# TEST_PROD_BATT_PANEL.net
KiCad netlist of a schematic drawn in EAGLE
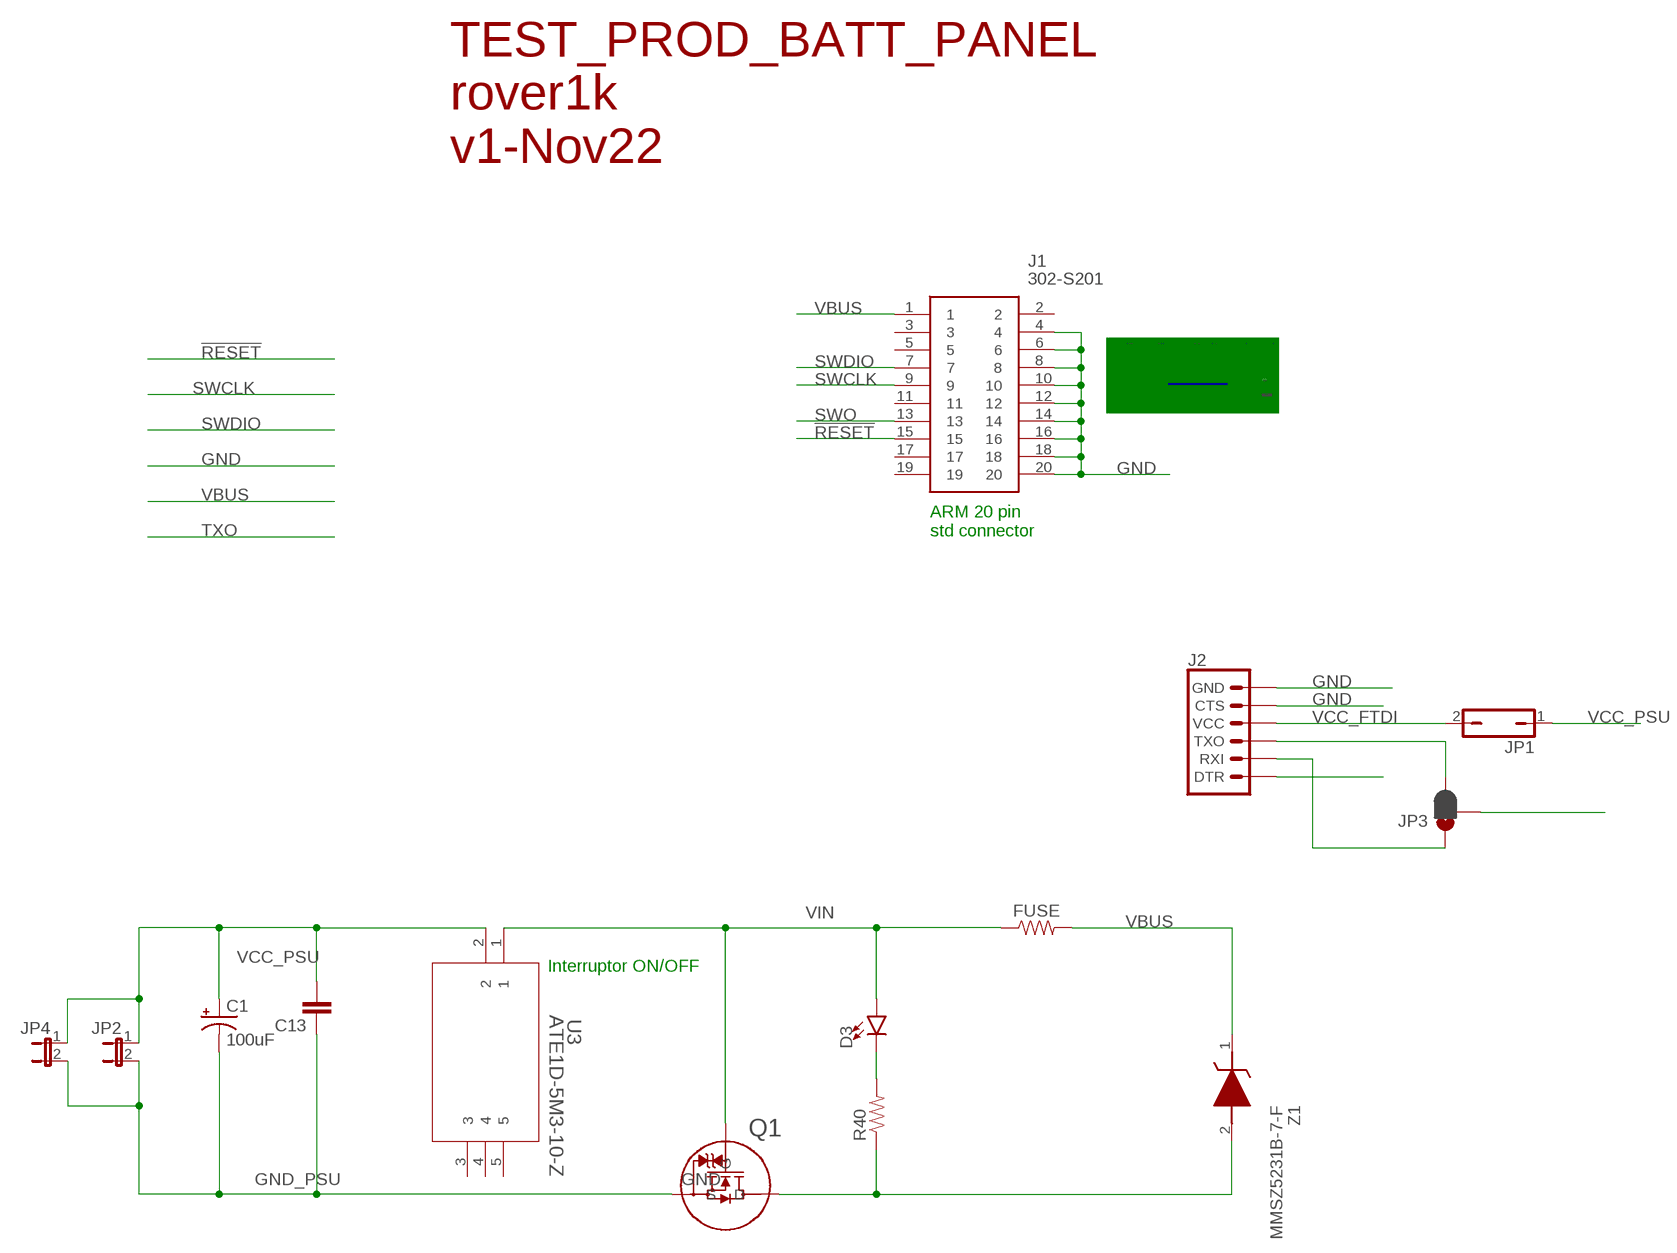
[diagram p0: schematic, sheet 1]

(export (version "E")
  (design (tool "Eeschema 10.0.6"))
  (components
    (comp (ref "C1")
      (value "100uF")
      (footprint "eagle-import:CPOL-RADIAL-2.5MM-6.5MM")
      (libsource (lib "eagle-import") (part "100UF-POLAR-RADIAL-2.5MM-25V-20%"))
    )
    (comp (ref "C13")
      (value "C-EUC0805")
      (footprint "eagle-import:C0805")
      (libsource (lib "eagle-import") (part "C-EUC0805"))
    )
    (comp (ref "D3")
      (value "LED3MM")
      (footprint "eagle-import:LED_3MM")
      (libsource (lib "eagle-import") (part "LED3MM"))
    )
    (comp (ref "FUSE")
      (value "RESISTOR0805")
      (footprint "eagle-import:0805")
      (libsource (lib "eagle-import") (part "RESISTOR0805"))
    )
    (comp (ref "J1")
      (value "302-S201")
      (footprint "eagle-import:SHDR20W66P254_2X10_3300X905X90")
      (libsource (lib "eagle-import") (part "302-S201"))
    )
    (comp (ref "J2")
      (value "6_PIN_SERIAL_TARGET")
      (footprint "eagle-import:1X06")
      (libsource (lib "eagle-import") (part "6_PIN_SERIAL_TARGET"))
    )
    (comp (ref "JP1")
      (value "JP1Q")
      (footprint "eagle-import:JP1")
      (libsource (lib "eagle-import") (part "JP1Q"))
    )
    (comp (ref "JP2")
      (value "JP1E")
      (footprint "eagle-import:JP1")
      (libsource (lib "eagle-import") (part "JP1E"))
    )
    (comp (ref "JP3")
      (value "JUMPER-SMT_3_1-NC_PASTE_NO-SILK")
      (footprint "eagle-import:SMT-JUMPER_3_1-NC_PASTE_NO-SILK")
      (libsource (lib "eagle-import") (part "JUMPER-SMT_3_1-NC_PASTE_NO-SILK"))
    )
    (comp (ref "JP4")
      (value "JP1E")
      (footprint "eagle-import:JP1")
      (libsource (lib "eagle-import") (part "JP1E"))
    )
    (comp (ref "Q1")
      (value "PJA3416AE_R1_00001")
      (footprint "eagle-import:SOT23_PJA3416_PNJ")
      (fields (field (name "COPYRIGHT") "Copyright (C) 2022 Ultra Librarian. All rights reserved."))
      (libsource (lib "eagle-import") (part "PJA3416AE_R1_00001"))
    )
    (comp (ref "R40")
      (value "10K")
      (footprint "eagle-import:0805")
      (libsource (lib "eagle-import") (part "RESISTOR0805-RES"))
    )
    (comp (ref "U3")
      (value "ATE1D-5M3-10-Z")
      (footprint "eagle-import:SPDT05_ATE1D_9P5X8_NDC")
      (fields (field (name "COPYRIGHT") "Copyright (C) 2022 Ultra Librarian. All rights reserved."))
      (libsource (lib "eagle-import") (part "ATE1D-5M3-10-Z"))
    )
    (comp (ref "Z1")
      (value "MMSZ5231B-7-F")
      (footprint "eagle-import:SOD3716X145N")
      (fields (field (name "MOUSER_PART_NUMBER") "621-MMSZ5231B-F"))
      (libsource (lib "eagle-import") (part "MMSZ5231B-7-F"))
    )
  )
  (nets
    (net (code "1") (name "/GND") (class "Default")
      (node (ref "J1") (pin "10") (pinfunction "10_10") (pintype "bidirectional"))
      (node (ref "J1") (pin "12") (pinfunction "12_12") (pintype "bidirectional"))
      (node (ref "J1") (pin "14") (pinfunction "14_14") (pintype "bidirectional"))
      (node (ref "J1") (pin "16") (pinfunction "16_16") (pintype "bidirectional"))
      (node (ref "J1") (pin "18") (pinfunction "18_18") (pintype "bidirectional"))
      (node (ref "J1") (pin "20") (pinfunction "20_20") (pintype "bidirectional"))
      (node (ref "J1") (pin "4") (pinfunction "4_4") (pintype "bidirectional"))
      (node (ref "J1") (pin "6") (pinfunction "6_6") (pintype "bidirectional"))
      (node (ref "J1") (pin "8") (pinfunction "8_8") (pintype "bidirectional"))
      (node (ref "J2") (pin "5") (pinfunction "CTS_5") (pintype "passive"))
      (node (ref "J2") (pin "6") (pinfunction "GND_6") (pintype "passive"))
      (node (ref "Q1") (pin "3") (pinfunction "D_3") (pintype "passive"))
      (node (ref "R40") (pin "1") (pinfunction "1_1") (pintype "passive"))
      (node (ref "Z1") (pin "2") (pinfunction "A_2") (pintype "bidirectional"))
    )
    (net (code "2") (name "/GND_PSU") (class "Default")
      (node (ref "C1") (pin "2") (pinfunction "-_2") (pintype "passive"))
      (node (ref "C13") (pin "1") (pinfunction "1_1") (pintype "passive"))
      (node (ref "JP2") (pin "2") (pinfunction "2_2") (pintype "passive"))
      (node (ref "JP4") (pin "2") (pinfunction "2_2") (pintype "passive"))
      (node (ref "Q1") (pin "2") (pinfunction "S_2") (pintype "passive"))
    )
    (net (code "3") (name "/SWCLK") (class "Default")
      (node (ref "J1") (pin "9") (pinfunction "9_9") (pintype "bidirectional"))
    )
    (net (code "4") (name "/SWDIO") (class "Default")
      (node (ref "J1") (pin "7") (pinfunction "7_7") (pintype "bidirectional"))
    )
    (net (code "5") (name "/SWO") (class "Default")
      (node (ref "J1") (pin "13") (pinfunction "13_13") (pintype "bidirectional"))
    )
    (net (code "6") (name "/TXO") (class "Default")
      (node (ref "JP3") (pin "2") (pinfunction "2_2") (pintype "passive"))
    )
    (net (code "7") (name "/VBUS") (class "Default")
      (node (ref "FUSE") (pin "2") (pinfunction "2_2") (pintype "passive"))
      (node (ref "J1") (pin "1") (pinfunction "1_1") (pintype "bidirectional"))
      (node (ref "Z1") (pin "1") (pinfunction "K_1") (pintype "bidirectional"))
    )
    (net (code "8") (name "/VCC_FTDI") (class "Default")
      (node (ref "J2") (pin "4") (pinfunction "VCC_4") (pintype "passive"))
      (node (ref "JP1") (pin "2") (pinfunction "2_2") (pintype "passive"))
    )
    (net (code "9") (name "/VCC_PSU") (class "Default")
      (node (ref "C1") (pin "1") (pinfunction "+_1") (pintype "passive"))
      (node (ref "C13") (pin "2") (pinfunction "2_2") (pintype "passive"))
      (node (ref "JP1") (pin "1") (pinfunction "1_1") (pintype "passive"))
      (node (ref "JP2") (pin "1") (pinfunction "1_1") (pintype "passive"))
      (node (ref "JP4") (pin "1") (pinfunction "1_1") (pintype "passive"))
      (node (ref "U3") (pin "2") (pinfunction "2_2") (pintype "passive"))
    )
    (net (code "10") (name "/VIN") (class "Default")
      (node (ref "D3") (pin "A") (pinfunction "A_A") (pintype "passive"))
      (node (ref "FUSE") (pin "1") (pinfunction "1_1") (pintype "passive"))
      (node (ref "Q1") (pin "1") (pinfunction "G_1") (pintype "passive"))
      (node (ref "U3") (pin "1") (pinfunction "1_1") (pintype "passive"))
    )
    (net (code "11") (name "/~{RESET}") (class "Default")
      (node (ref "J1") (pin "15") (pinfunction "15_15") (pintype "bidirectional"))
    )
    (net (code "12") (name "Net-(D3-C)") (class "Default")
      (node (ref "D3") (pin "K") (pinfunction "C_K") (pintype "passive"))
      (node (ref "R40") (pin "2") (pinfunction "2_2") (pintype "passive"))
    )
    (net (code "13") (name "Net-(J2-RXI)") (class "Default")
      (node (ref "J2") (pin "2") (pinfunction "RXI_2") (pintype "passive"))
      (node (ref "JP3") (pin "1") (pinfunction "1_1") (pintype "passive"))
    )
    (net (code "14") (name "Net-(J2-TXO)") (class "Default")
      (node (ref "J2") (pin "3") (pinfunction "TXO_3") (pintype "passive"))
      (node (ref "JP3") (pin "3") (pinfunction "3_3") (pintype "passive"))
    )
    (net (code "15") (name "unconnected-(J1-Pad2)") (class "Default")
      (node (ref "J1") (pin "2") (pinfunction "2_2") (pintype "bidirectional"))
    )
    (net (code "16") (name "unconnected-(J1-Pad3)") (class "Default")
      (node (ref "J1") (pin "3") (pinfunction "3_3") (pintype "bidirectional"))
    )
    (net (code "17") (name "unconnected-(J1-Pad5)") (class "Default")
      (node (ref "J1") (pin "5") (pinfunction "5_5") (pintype "bidirectional"))
    )
    (net (code "18") (name "unconnected-(J1-Pad11)") (class "Default")
      (node (ref "J1") (pin "11") (pinfunction "11_11") (pintype "bidirectional"))
    )
    (net (code "19") (name "unconnected-(J1-Pad17)") (class "Default")
      (node (ref "J1") (pin "17") (pinfunction "17_17") (pintype "bidirectional"))
    )
    (net (code "20") (name "unconnected-(J1-Pad19)") (class "Default")
      (node (ref "J1") (pin "19") (pinfunction "19_19") (pintype "bidirectional"))
    )
    (net (code "21") (name "unconnected-(J2-DTR-Pad1)") (class "Default")
      (node (ref "J2") (pin "1") (pinfunction "DTR_1") (pintype "passive"))
    )
    (net (code "22") (name "unconnected-(U3-Pad3)") (class "Default")
      (node (ref "U3") (pin "3") (pinfunction "3_3") (pintype "passive"))
    )
    (net (code "23") (name "unconnected-(U3-Pad4)") (class "Default")
      (node (ref "U3") (pin "4") (pinfunction "4_4") (pintype "passive"))
    )
    (net (code "24") (name "unconnected-(U3-Pad5)") (class "Default")
      (node (ref "U3") (pin "5") (pinfunction "5_5") (pintype "passive"))
    )
  )
)
